# USB_TypeC_DRP.net
KiCad netlist of a schematic drawn in Altium Designer
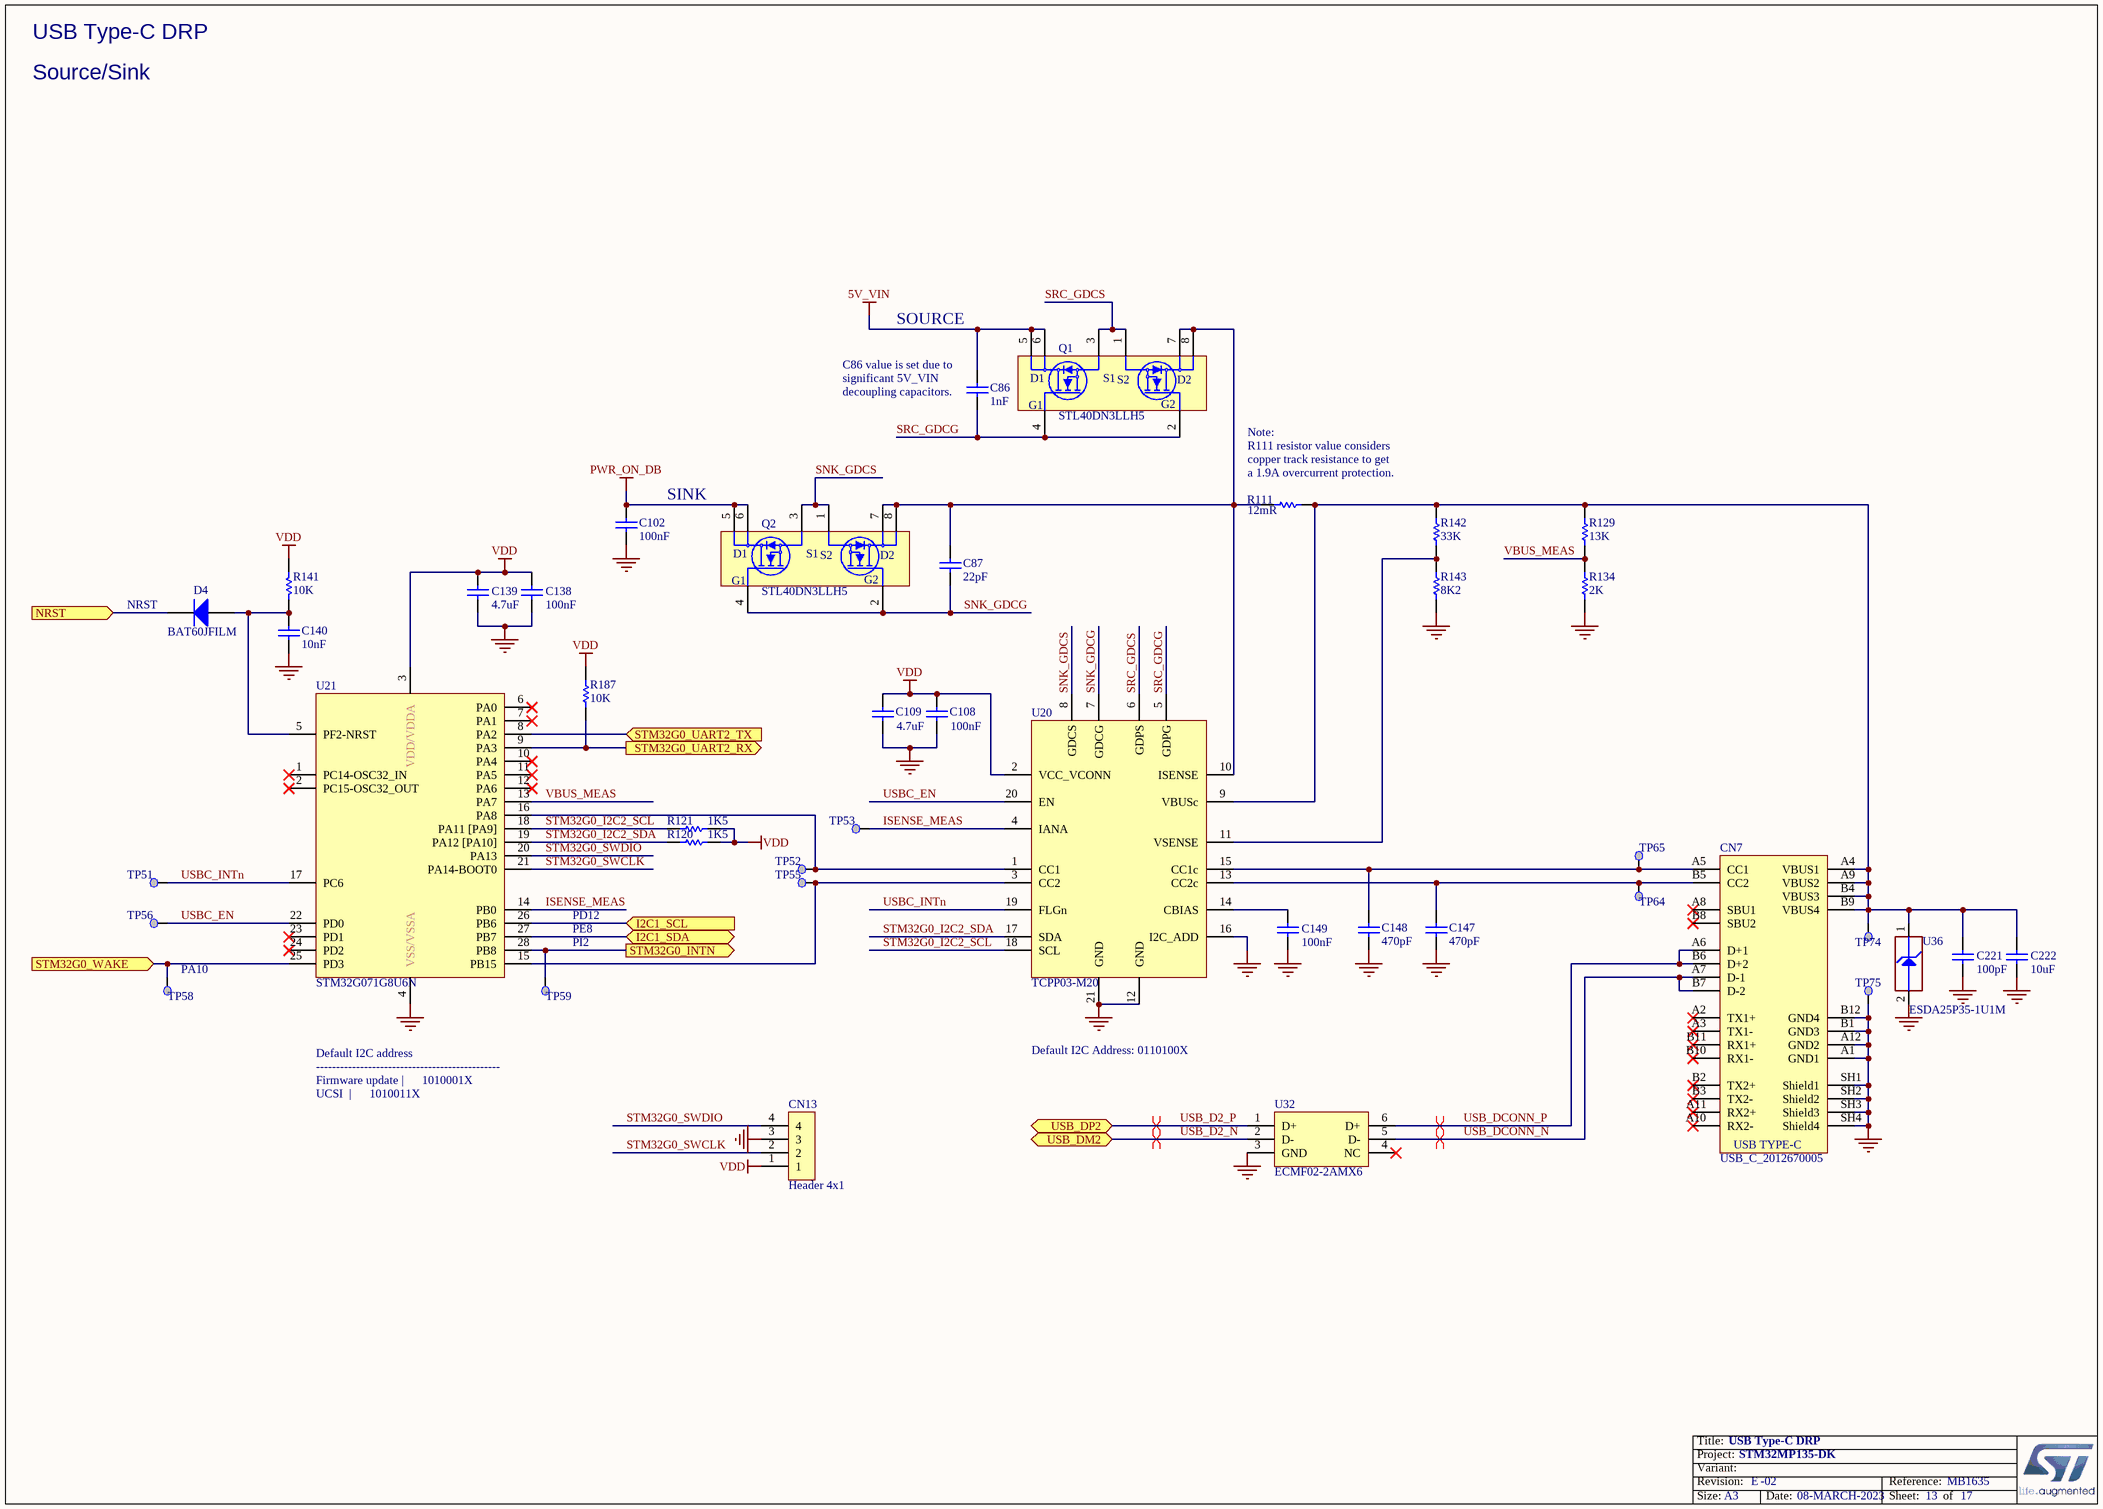
[diagram p0: USB_TypeC_DRP.SchDoc]

(export (version "E")
  (design (tool "Eeschema 10.0.6"))
  (components
    (comp (ref "C86")
      (value "1nF")
      (footprint "C0402")
      (description "Capacitor, MLCC, 1nF, 16V, X7R, +/-10%, 0402, T=0.5mm")
      (fields (field (name "INTERNAL_PART_NUMBER") "MCD-00198") (field (name "MANUFACTURER") "YAGEO"))
      (libsource (lib "MCD_PARTS_database") (part "Capacitor"))
    )
    (comp (ref "C87")
      (value "22pF")
      (footprint "C0402")
      (description "Capacitor, MLCC, 22pF, 50V, C0G, +/-5%, 0402, T=0.5mm")
      (fields (field (name "INTERNAL_PART_NUMBER") "MCD-01995") (field (name "MANUFACTURER") "TDK"))
      (libsource (lib "MCD_PARTS_database") (part "Capacitor"))
    )
    (comp (ref "C102")
      (value "100nF")
      (footprint "C0402")
      (description "Capacitor, MLCC, 100nF, 16V, X7R, +/-10%, 0402, T=0.5mm")
      (fields (field (name "INTERNAL_PART_NUMBER") "MCD-00006") (field (name "MANUFACTURER") "YAGEO"))
      (libsource (lib "MCD_PARTS_database") (part "Capacitor"))
    )
    (comp (ref "C108")
      (value "100nF")
      (footprint "C0402")
      (description "Capacitor, MLCC, 100nF, 16V, X7R, +/-10%, 0402, T=0.5mm")
      (fields (field (name "INTERNAL_PART_NUMBER") "MCD-00006") (field (name "MANUFACTURER") "YAGEO"))
      (libsource (lib "MCD_PARTS_database") (part "Capacitor"))
    )
    (comp (ref "C109")
      (value "4.7uF")
      (footprint "C0402")
      (description "Capacitor, MLCC, 4.7uF, 6V3, X5R, +/-20%, 0402, T=0.5mm")
      (fields (field (name "INTERNAL_PART_NUMBER") "MCD-01356") (field (name "MANUFACTURER") "MURATA"))
      (libsource (lib "MCD_PARTS_database") (part "Capacitor"))
    )
    (comp (ref "C138")
      (value "100nF")
      (footprint "C0402")
      (description "Capacitor, MLCC, 100nF, 16V, X7R, +/-10%, 0402, T=0.5mm")
      (fields (field (name "INTERNAL_PART_NUMBER") "MCD-00006") (field (name "MANUFACTURER") "YAGEO"))
      (libsource (lib "MCD_PARTS_database") (part "Capacitor"))
    )
    (comp (ref "C139")
      (value "4.7uF")
      (footprint "C0402")
      (description "Capacitor, MLCC, 4.7uF, 6V3, X5R, +/-20%, 0402, T=0.5mm")
      (fields (field (name "INTERNAL_PART_NUMBER") "MCD-01356") (field (name "MANUFACTURER") "MURATA"))
      (libsource (lib "MCD_PARTS_database") (part "Capacitor"))
    )
    (comp (ref "C140")
      (value "10nF")
      (footprint "C0402")
      (description "Capacitor, MLCC, 10nF, 50V, X7R, +/-10%, 0402, T=0.5mm")
      (fields (field (name "INTERNAL_PART_NUMBER") "MCD-02198") (field (name "MANUFACTURER") "YAGEO"))
      (libsource (lib "MCD_PARTS_database") (part "Capacitor"))
    )
    (comp (ref "C147")
      (value "470pF")
      (footprint "C0402")
      (description "Capacitor, MLCC, 470pF, 50V, NPO, +/-5%, 0402, T=0.5mm")
      (fields
        (field (name "INTERNAL_PART_NUMBER") "MCD-00724")
        (field (name "MANUFACTURER_PART_NUMBER") "CC0402JRNPO9BN471")
      )
      (libsource (lib "MCD_PARTS_database") (part "Capacitor"))
    )
    (comp (ref "C148")
      (value "470pF")
      (footprint "C0402")
      (description "Capacitor, MLCC, 470pF, 50V, NPO, +/-5%, 0402, T=0.5mm")
      (fields
        (field (name "INTERNAL_PART_NUMBER") "MCD-00724")
        (field (name "MANUFACTURER_PART_NUMBER") "CC0402JRNPO9BN471")
      )
      (libsource (lib "MCD_PARTS_database") (part "Capacitor"))
    )
    (comp (ref "C149")
      (value "100nF")
      (footprint "C0603")
      (description "Capacitor, MLCC, 100nF, 50V, X7R, +/-10%, 0603, T=0.8mm")
      (fields (field (name "INTERNAL_PART_NUMBER") "MCD-01099") (field (name "BMS_PART_NUMBER") "9142278"))
      (libsource (lib "MCD_PARTS_database") (part "Capacitor"))
    )
    (comp (ref "C221")
      (value "100pF")
      (footprint "C0402")
      (description "Capacitor, MLCC, 100pF, 50V, NPO, +/-5%, 0402, T=0.5mm")
      (fields
        (field (name "INTERNAL_PART_NUMBER") "MCD-00205")
        (field (name "MANUFACTURER_PART_NUMBER") "CC0402JRNPO9BN101")
      )
      (libsource (lib "MCD_PARTS_database") (part "Capacitor"))
    )
    (comp (ref "C222")
      (value "10uF")
      (footprint "C1210")
      (description "Capacitor, MLCC, 10uF, 50V, X7R, +/-10%, 1210, T=2.5mm")
      (fields
        (field (name "INTERNAL_PART_NUMBER") "MCD-02378")
        (field (name "MANUFACTURER_PART_NUMBER") "C3225X7R1H106K250AC")
      )
      (libsource (lib "MCD_PARTS_database") (part "Capacitor"))
    )
    (comp (ref "CN7")
      (value "USB_C_2012670005")
      (footprint "CON_USB-TYPEC_MOLEX_2012670005")
      (description "USB_TypeC, 24 pins, RA, SMD, T=3.71mm (USB Certified 3.1)")
      (fields
        (field (name "INTERNAL_PART_NUMBER") "MCD-02421")
        (field (name "MANUFACTURER_PART_NUMBER") "2012670005")
      )
      (libsource (lib "MCD_PARTS_database") (part "USB_TYPE_C_Receptacle"))
    )
    (comp (ref "CN13")
      (value "Header 4x1")
      (footprint "CON_SAMTEC_TSW-104-07-G-S")
      (description "Header, 4x1, 2.54mm, VR, TH, T=5.84mm/2.54mm")
      (fields
        (field (name "INTERNAL_PART_NUMBER") "MCD-00029")
        (field (name "MANUFACTURER_PART_NUMBER") "TSW-104-07-G-S")
      )
      (libsource (lib "MCD_PARTS_database") (part "Header 4x1"))
    )
    (comp (ref "D4")
      (value "BAT60JFILM")
      (footprint "DIO_SOD323")
      (fields
        (field (name "INTERNAL_PART_NUMBER") "MCD-00034")
        (field (name "BMS_PART_NUMBER") "9151097")
        (field (name "MANUFACTURER") "STMICROELECTRONICS")
      )
      (libsource (lib "MCD_PARTS_database") (part "BAT60JFILM"))
    )
    (comp (ref "Q1")
      (value "STL40DN3LLH5")
      (footprint "PowerFLAT_5x6")
      (description "MOSFET, Dual N-channel 30 V, 0.016 Ω typ., 40 A, STripFET™ H5 Power MOSFET")
      (fields
        (field (name "INTERNAL_PART_NUMBER") "MCD-02152")
        (field (name "MANUFACTURER") "STMICROELECTRONICS")
      )
      (libsource (lib "MCD_PARTS_database") (part "STL40DN3LLH5"))
    )
    (comp (ref "Q2")
      (value "STL40DN3LLH5")
      (footprint "PowerFLAT_5x6")
      (description "MOSFET, Dual N-channel 30 V, 0.016 Ω typ., 40 A, STripFET™ H5 Power MOSFET")
      (fields
        (field (name "INTERNAL_PART_NUMBER") "MCD-02152")
        (field (name "MANUFACTURER") "STMICROELECTRONICS")
      )
      (libsource (lib "MCD_PARTS_database") (part "STL40DN3LLH5"))
    )
    (comp (ref "R111")
      (value "12mR")
      (footprint "R0603_H070")
      (description "Resistor, 12mR, 0603, +/-1%, 1/2W")
      (fields (field (name "INTERNAL_PART_NUMBER") "MCD-03129") (field (name "MANUFACTURER") "VISHAY"))
      (libsource (lib "MCD_PARTS_database") (part "Resistor"))
    )
    (comp (ref "R120")
      (value "1K5")
      (footprint "R0402")
      (description "Resistor, 1K5, 0402, +/-1%, 1/16W")
      (fields (field (name "INTERNAL_PART_NUMBER") "MCD-00068") (field (name "MANUFACTURER") "YAGEO"))
      (libsource (lib "MCD_PARTS_database") (part "Resistor"))
    )
    (comp (ref "R121")
      (value "1K5")
      (footprint "R0402")
      (description "Resistor, 1K5, 0402, +/-1%, 1/16W")
      (fields (field (name "INTERNAL_PART_NUMBER") "MCD-00068") (field (name "MANUFACTURER") "YAGEO"))
      (libsource (lib "MCD_PARTS_database") (part "Resistor"))
    )
    (comp (ref "R129")
      (value "13K")
      (footprint "R0603")
      (description "Resistor, 13K, 0603,+/-1%, 1/10W")
      (fields (field (name "INTERNAL_PART_NUMBER") "MCD-00384") (field (name "MANUFACTURER") "YAGEO"))
      (libsource (lib "MCD_PARTS_database") (part "Resistor"))
    )
    (comp (ref "R134")
      (value "2K")
      (footprint "R0603")
      (description "Resistor, 2K ,0603, +/-1%, 1/10W")
      (fields (field (name "INTERNAL_PART_NUMBER") "MCD-00420") (field (name "MANUFACTURER") "YAGEO"))
      (libsource (lib "MCD_PARTS_database") (part "Resistor"))
    )
    (comp (ref "R141")
      (value "10K")
      (footprint "R0402")
      (description "Resistor, 10K, 0402, +/-1%, 1/16W")
      (fields (field (name "INTERNAL_PART_NUMBER") "MCD-00053") (field (name "BMS_PART_NUMBER") "9131590"))
      (libsource (lib "MCD_PARTS_database") (part "Resistor"))
    )
    (comp (ref "R142")
      (value "33K")
      (footprint "R0603")
      (description "Resistor, 33K, 0603, +/-1%, 1/10W")
      (fields (field (name "INTERNAL_PART_NUMBER") "MCD-00259") (field (name "BMS_PART_NUMBER") "9129771"))
      (libsource (lib "MCD_PARTS_database") (part "Resistor"))
    )
    (comp (ref "R143")
      (value "8K2")
      (footprint "R0603")
      (description "Resistor, 8K2, 0603, +/-1%, 1/10W")
      (fields (field (name "INTERNAL_PART_NUMBER") "MCD-00530") (field (name "MANUFACTURER") "YAGEO"))
      (libsource (lib "MCD_PARTS_database") (part "Resistor"))
    )
    (comp (ref "R187")
      (value "10K")
      (footprint "R0402")
      (description "Resistor, 10K, 0402, +/-1%, 1/16W")
      (fields
        (field (name "INTERNAL_PART_NUMBER") "MCD-00053")
        (field (name "MANUFACTURER_PART_NUMBER") "RC0402FR-0710KL")
      )
      (libsource (lib "MCD_PARTS_database") (part "Resistor"))
    )
    (comp (ref "TP51")
      (value "Test Point")
      (footprint "TP_SMD_1MM")
      (description "Test Point 1mm")
      (fields (field (name "INTERNAL_PART_NUMBER") "MCD-00074"))
      (libsource (lib "") (part "Test Point_2"))
    )
    (comp (ref "TP52")
      (value "Test Point")
      (footprint "TP_SMD_1MM")
      (description "Test Point 1mm")
      (fields (field (name "INTERNAL_PART_NUMBER") "MCD-00074"))
      (libsource (lib "") (part "Test Point_2"))
    )
    (comp (ref "TP53")
      (value "Test Point")
      (footprint "TP_SMD_1MM")
      (description "Test Point 1mm")
      (fields (field (name "INTERNAL_PART_NUMBER") "MCD-00074"))
      (libsource (lib "") (part "Test Point_2"))
    )
    (comp (ref "TP55")
      (value "Test Point")
      (footprint "TP_SMD_1MM")
      (description "Test Point 1mm")
      (fields (field (name "INTERNAL_PART_NUMBER") "MCD-00074"))
      (libsource (lib "") (part "Test Point_2"))
    )
    (comp (ref "TP56")
      (value "Test Point")
      (footprint "TP_SMD_1MM")
      (description "Test Point 1mm")
      (fields (field (name "INTERNAL_PART_NUMBER") "MCD-00074"))
      (libsource (lib "") (part "Test Point_2"))
    )
    (comp (ref "TP58")
      (value "Test Point")
      (footprint "TP_SMD_1MM")
      (description "Test Point 1mm")
      (fields (field (name "INTERNAL_PART_NUMBER") "MCD-00074"))
      (libsource (lib "MCD_PARTS_database") (part "Test Point"))
    )
    (comp (ref "TP59")
      (value "Test Point")
      (footprint "TP_SMD_1MM")
      (description "Test Point 1mm")
      (fields (field (name "INTERNAL_PART_NUMBER") "MCD-00074"))
      (libsource (lib "MCD_PARTS_database") (part "Test Point"))
    )
    (comp (ref "TP64")
      (value "Test Point")
      (footprint "TP_SMD_1MM")
      (description "Test Point 1mm")
      (fields (field (name "INTERNAL_PART_NUMBER") "MCD-00074"))
      (libsource (lib "MCD_PARTS_database") (part "Test Point"))
    )
    (comp (ref "TP65")
      (value "Test Point")
      (footprint "TP_SMD_1MM")
      (description "Test Point 1mm")
      (fields (field (name "INTERNAL_PART_NUMBER") "MCD-00074"))
      (libsource (lib "") (part "Test Point_1"))
    )
    (comp (ref "TP74")
      (value "Test Point")
      (footprint "TP_SMD_1MM")
      (description "Test Point 1mm")
      (fields (field (name "INTERNAL_PART_NUMBER") "MCD-00074"))
      (libsource (lib "MCD_PARTS_database") (part "Test Point"))
    )
    (comp (ref "TP75")
      (value "Test Point")
      (footprint "TP_SMD_1MM")
      (description "Test Point 1mm")
      (fields (field (name "INTERNAL_PART_NUMBER") "MCD-00074"))
      (libsource (lib "") (part "Test Point_1"))
    )
    (comp (ref "U20")
      (value "TCPP03-M20")
      (footprint "ICC_QFN20-EPAD_4X4_P050")
      (description "USB Type-C Port Protection for USB DRP Power Delivery, PPS compliant")
      (fields
        (field (name "INTERNAL_PART_NUMBER") "MCD-02130")
        (field (name "MANUFACTURER") "STMICROELECTRONICS")
      )
      (libsource (lib "MCD_PARTS_database") (part "TCPP03-M20"))
    )
    (comp (ref "U21")
      (value "STM32G071G8U6N")
      (footprint "ICC_UFQFPN28_4X4_P050")
      (fields
        (field (name "INTERNAL_PART_NUMBER") "MCD-02218")
        (field (name "MANUFACTURER") "STMICROELECTRONICS")
      )
      (libsource (lib "MCD_PARTS_database") (part "STM32G071G8U6N"))
    )
    (comp (ref "U32")
      (value "ECMF02-2AMX6")
      (footprint "ESD_QFN-6L_1P7X1P5_P050")
      (description "Common mode filter with ESD protection for USB 2.0 interface")
      (fields
        (field (name "INTERNAL_PART_NUMBER") "MCD-00649")
        (field (name "MANUFACTURER") "STMICROELECTRONICS")
      )
      (libsource (lib "MCD_PARTS_database") (part "ECMF02-2AMX6"))
    )
    (comp (ref "U36")
      (value "ESDA25P35-1U1M")
      (footprint "ESD_QFN1610_2N_1K_2A")
      (description "High power Transient voltage suppressor:25V/35A EOS and ESD transients protection.")
      (fields
        (field (name "INTERNAL_PART_NUMBER") "MCD-01207")
        (field (name "MANUFACTURER") "STMICROELECTRONICS")
      )
      (libsource (lib "MCD_PARTS_database") (part "ESD-TRANSIL"))
    )
  )
  (nets
    (net (code "1") (name "/I2C1_SCL") (class "Default")
      (node (ref "U21") (pin "26") (pinfunction "PB6_26") (pintype "passive"))
    )
    (net (code "2") (name "/I2C1_SDA") (class "Default")
      (node (ref "U21") (pin "27") (pinfunction "PB7_27") (pintype "passive"))
    )
    (net (code "3") (name "/ISENSE_MEAS") (class "Default")
      (node (ref "TP53") (pin "1") (pinfunction "1_1") (pintype "passive"))
      (node (ref "U20") (pin "4") (pinfunction "IANA_4") (pintype "passive"))
      (node (ref "U21") (pin "14") (pinfunction "PB0_14") (pintype "passive"))
    )
    (net (code "4") (name "/NRST") (class "Default")
      (node (ref "D4") (pin "2") (pinfunction "K_2") (pintype "passive"))
    )
    (net (code "5") (name "/SNK_GDCG") (class "Default")
      (node (ref "C87") (pin "1") (pinfunction "1_1") (pintype "passive"))
      (node (ref "Q2") (pin "2") (pinfunction "G2_2") (pintype "passive"))
      (node (ref "Q2") (pin "4") (pinfunction "G1_4") (pintype "passive"))
      (node (ref "U20") (pin "7") (pinfunction "GDCG_7") (pintype "passive"))
    )
    (net (code "6") (name "/SNK_GDCS") (class "Default")
      (node (ref "Q2") (pin "1") (pinfunction "S2_1") (pintype "passive"))
      (node (ref "Q2") (pin "3") (pinfunction "S1_3") (pintype "passive"))
      (node (ref "U20") (pin "8") (pinfunction "GDCS_8") (pintype "passive"))
    )
    (net (code "7") (name "/SRC_GDCG") (class "Default")
      (node (ref "C86") (pin "1") (pinfunction "1_1") (pintype "passive"))
      (node (ref "Q1") (pin "2") (pinfunction "G2_2") (pintype "passive"))
      (node (ref "Q1") (pin "4") (pinfunction "G1_4") (pintype "passive"))
      (node (ref "U20") (pin "5") (pinfunction "GDPG_5") (pintype "passive"))
    )
    (net (code "8") (name "/SRC_GDCS") (class "Default")
      (node (ref "Q1") (pin "1") (pinfunction "S2_1") (pintype "passive"))
      (node (ref "Q1") (pin "3") (pinfunction "S1_3") (pintype "passive"))
      (node (ref "U20") (pin "6") (pinfunction "GDPS_6") (pintype "passive"))
    )
    (net (code "9") (name "/STM32G0_I2C2_SCL") (class "Default")
      (node (ref "R121") (pin "2") (pinfunction "2_2") (pintype "passive"))
      (node (ref "U20") (pin "18") (pinfunction "SCL_18") (pintype "passive"))
      (node (ref "U21") (pin "18") (pinfunction "PA11_[PA9]_18") (pintype "passive"))
    )
    (net (code "10") (name "/STM32G0_I2C2_SDA") (class "Default")
      (node (ref "R120") (pin "1") (pinfunction "1_1") (pintype "passive"))
      (node (ref "U20") (pin "17") (pinfunction "SDA_17") (pintype "passive"))
      (node (ref "U21") (pin "19") (pinfunction "PA12_[PA10]_19") (pintype "passive"))
    )
    (net (code "11") (name "/STM32G0_INTN") (class "Default")
      (node (ref "TP59") (pin "1") (pinfunction "1_1") (pintype "passive"))
      (node (ref "U21") (pin "28") (pinfunction "PB8_28") (pintype "passive"))
    )
    (net (code "12") (name "/STM32G0_SWCLK") (class "Default")
      (node (ref "CN13") (pin "2") (pinfunction "2_2") (pintype "passive"))
      (node (ref "U21") (pin "21") (pinfunction "PA14-BOOT0_21") (pintype "passive"))
    )
    (net (code "13") (name "/STM32G0_SWDIO") (class "Default")
      (node (ref "CN13") (pin "4") (pinfunction "4_4") (pintype "passive"))
      (node (ref "U21") (pin "20") (pinfunction "PA13_20") (pintype "passive"))
    )
    (net (code "14") (name "/STM32G0_UART2_RX") (class "Default")
      (node (ref "R187") (pin "1") (pinfunction "1_1") (pintype "passive"))
      (node (ref "U21") (pin "9") (pinfunction "PA3_9") (pintype "passive"))
    )
    (net (code "15") (name "/STM32G0_UART2_TX") (class "Default")
      (node (ref "U21") (pin "8") (pinfunction "PA2_8") (pintype "passive"))
    )
    (net (code "16") (name "/STM32G0_WAKE") (class "Default")
      (node (ref "TP58") (pin "1") (pinfunction "1_1") (pintype "passive"))
      (node (ref "U21") (pin "25") (pinfunction "PD3_25") (pintype "passive"))
    )
    (net (code "17") (name "/USBC_EN") (class "Default")
      (node (ref "TP56") (pin "1") (pinfunction "1_1") (pintype "passive"))
      (node (ref "U20") (pin "20") (pinfunction "EN_20") (pintype "passive"))
      (node (ref "U21") (pin "22") (pinfunction "PD0_22") (pintype "passive"))
    )
    (net (code "18") (name "/USBC_INTn") (class "Default")
      (node (ref "TP51") (pin "1") (pinfunction "1_1") (pintype "passive"))
      (node (ref "U20") (pin "19") (pinfunction "FLGn_19") (pintype "passive"))
      (node (ref "U21") (pin "17") (pinfunction "PC6_17") (pintype "passive"))
    )
    (net (code "19") (name "/USB_D2_N") (class "Default")
      (node (ref "U32") (pin "2") (pinfunction "D-_2") (pintype "passive"))
    )
    (net (code "20") (name "/USB_D2_P") (class "Default")
      (node (ref "U32") (pin "1") (pinfunction "D+_1") (pintype "passive"))
    )
    (net (code "21") (name "/USB_DCONN_N") (class "Default")
      (node (ref "CN7") (pin "A7") (pinfunction "D-1_A7") (pintype "passive"))
      (node (ref "CN7") (pin "B7") (pinfunction "D-2_B7") (pintype "passive"))
      (node (ref "U32") (pin "5") (pinfunction "D-_5") (pintype "passive"))
    )
    (net (code "22") (name "/USB_DCONN_P") (class "Default")
      (node (ref "CN7") (pin "A6") (pinfunction "D+1_A6") (pintype "passive"))
      (node (ref "CN7") (pin "B6") (pinfunction "D+2_B6") (pintype "passive"))
      (node (ref "U32") (pin "6") (pinfunction "D+_6") (pintype "passive"))
    )
    (net (code "23") (name "/VBUS_MEAS") (class "Default")
      (node (ref "R129") (pin "1") (pinfunction "1_1") (pintype "passive"))
      (node (ref "R134") (pin "2") (pinfunction "2_2") (pintype "passive"))
      (node (ref "U21") (pin "13") (pinfunction "PA7_13") (pintype "passive"))
    )
    (net (code "24") (name "5V_VIN") (class "Default")
      (node (ref "C86") (pin "2") (pinfunction "2_2") (pintype "passive"))
      (node (ref "Q1") (pin "5") (pinfunction "D1_5") (pintype "passive"))
      (node (ref "Q1") (pin "6") (pinfunction "D1_6") (pintype "passive"))
    )
    (net (code "25") (name "GND") (class "Default")
      (node (ref "C102") (pin "1") (pinfunction "1_1") (pintype "passive"))
      (node (ref "C108") (pin "1") (pinfunction "1_1") (pintype "passive"))
      (node (ref "C109") (pin "1") (pinfunction "1_1") (pintype "passive"))
      (node (ref "C138") (pin "1") (pinfunction "1_1") (pintype "passive"))
      (node (ref "C139") (pin "1") (pinfunction "1_1") (pintype "passive"))
      (node (ref "C140") (pin "1") (pinfunction "1_1") (pintype "passive"))
      (node (ref "C147") (pin "1") (pinfunction "1_1") (pintype "passive"))
      (node (ref "C148") (pin "1") (pinfunction "1_1") (pintype "passive"))
      (node (ref "C149") (pin "1") (pinfunction "1_1") (pintype "passive"))
      (node (ref "C221") (pin "1") (pinfunction "1_1") (pintype "passive"))
      (node (ref "C222") (pin "1") (pinfunction "1_1") (pintype "passive"))
      (node (ref "CN13") (pin "3") (pinfunction "3_3") (pintype "passive"))
      (node (ref "CN7") (pin "A1") (pinfunction "GND1_A1") (pintype "passive"))
      (node (ref "CN7") (pin "A12") (pinfunction "GND2_A12") (pintype "passive"))
      (node (ref "CN7") (pin "B1") (pinfunction "GND3_B1") (pintype "passive"))
      (node (ref "CN7") (pin "B12") (pinfunction "GND4_B12") (pintype "passive"))
      (node (ref "CN7") (pin "SH1") (pinfunction "Shield1_SH1") (pintype "passive"))
      (node (ref "CN7") (pin "SH2") (pinfunction "Shield2_SH2") (pintype "passive"))
      (node (ref "CN7") (pin "SH3") (pinfunction "Shield3_SH3") (pintype "passive"))
      (node (ref "CN7") (pin "SH4") (pinfunction "Shield4_SH4") (pintype "passive"))
      (node (ref "R134") (pin "1") (pinfunction "1_1") (pintype "passive"))
      (node (ref "R143") (pin "1") (pinfunction "1_1") (pintype "passive"))
      (node (ref "TP75") (pin "1") (pinfunction "1_1") (pintype "passive"))
      (node (ref "U20") (pin "12") (pinfunction "GND_12") (pintype "passive"))
      (node (ref "U20") (pin "16") (pinfunction "I2C_ADD_16") (pintype "passive"))
      (node (ref "U20") (pin "21") (pinfunction "GND_21") (pintype "passive"))
      (node (ref "U21") (pin "4") (pinfunction "VSS/VSSA_4") (pintype "passive"))
      (node (ref "U32") (pin "3") (pinfunction "GND_3") (pintype "passive"))
      (node (ref "U36") (pin "2") (pinfunction "GND_2") (pintype "passive"))
    )
    (net (code "26") (name "Net-(CN7-CC1)") (class "Default")
      (node (ref "C148") (pin "2") (pinfunction "2_2") (pintype "passive"))
      (node (ref "CN7") (pin "A5") (pinfunction "CC1_A5") (pintype "passive"))
      (node (ref "TP65") (pin "1") (pinfunction "1_1") (pintype "passive"))
      (node (ref "U20") (pin "15") (pinfunction "CC1c_15") (pintype "passive"))
    )
    (net (code "27") (name "Net-(CN7-CC2)") (class "Default")
      (node (ref "C147") (pin "2") (pinfunction "2_2") (pintype "passive"))
      (node (ref "CN7") (pin "B5") (pinfunction "CC2_B5") (pintype "passive"))
      (node (ref "TP64") (pin "1") (pinfunction "1_1") (pintype "passive"))
      (node (ref "U20") (pin "13") (pinfunction "CC2c_13") (pintype "passive"))
    )
    (net (code "28") (name "Net-(CN7-VBUS1)") (class "Default")
      (node (ref "C221") (pin "2") (pinfunction "2_2") (pintype "passive"))
      (node (ref "C222") (pin "2") (pinfunction "2_2") (pintype "passive"))
      (node (ref "CN7") (pin "A4") (pinfunction "VBUS1_A4") (pintype "passive"))
      (node (ref "CN7") (pin "A9") (pinfunction "VBUS2_A9") (pintype "passive"))
      (node (ref "CN7") (pin "B4") (pinfunction "VBUS3_B4") (pintype "passive"))
      (node (ref "CN7") (pin "B9") (pinfunction "VBUS4_B9") (pintype "passive"))
      (node (ref "R111") (pin "1") (pinfunction "1_1") (pintype "passive"))
      (node (ref "R129") (pin "2") (pinfunction "2_2") (pintype "passive"))
      (node (ref "R142") (pin "2") (pinfunction "2_2") (pintype "passive"))
      (node (ref "TP74") (pin "1") (pinfunction "1_1") (pintype "passive"))
      (node (ref "U20") (pin "9") (pinfunction "VBUSc_9") (pintype "passive"))
      (node (ref "U36") (pin "1") (pinfunction "IO1_1") (pintype "passive"))
    )
    (net (code "29") (name "Net-(D4-A)") (class "Default")
      (node (ref "C140") (pin "2") (pinfunction "2_2") (pintype "passive"))
      (node (ref "D4") (pin "1") (pinfunction "A_1") (pintype "passive"))
      (node (ref "R141") (pin "1") (pinfunction "1_1") (pintype "passive"))
      (node (ref "U21") (pin "5") (pinfunction "PF2-NRST_5") (pintype "passive"))
    )
    (net (code "30") (name "Net-(U20-CBIAS)") (class "Default")
      (node (ref "C149") (pin "2") (pinfunction "2_2") (pintype "passive"))
      (node (ref "U20") (pin "14") (pinfunction "CBIAS_14") (pintype "passive"))
    )
    (net (code "31") (name "Net-(U20-CC1)") (class "Default")
      (node (ref "TP52") (pin "1") (pinfunction "1_1") (pintype "passive"))
      (node (ref "U20") (pin "1") (pinfunction "CC1_1") (pintype "passive"))
      (node (ref "U21") (pin "16") (pinfunction "PA8_16") (pintype "passive"))
    )
    (net (code "32") (name "Net-(U20-CC2)") (class "Default")
      (node (ref "TP55") (pin "1") (pinfunction "1_1") (pintype "passive"))
      (node (ref "U20") (pin "3") (pinfunction "CC2_3") (pintype "passive"))
      (node (ref "U21") (pin "15") (pinfunction "PB15_15") (pintype "passive"))
    )
    (net (code "33") (name "Net-(U20-ISENSE)") (class "Default")
      (node (ref "C87") (pin "2") (pinfunction "2_2") (pintype "passive"))
      (node (ref "Q1") (pin "7") (pinfunction "D2_7") (pintype "passive"))
      (node (ref "Q1") (pin "8") (pinfunction "D2_8") (pintype "passive"))
      (node (ref "Q2") (pin "7") (pinfunction "D2_7") (pintype "passive"))
      (node (ref "Q2") (pin "8") (pinfunction "D2_8") (pintype "passive"))
      (node (ref "R111") (pin "2") (pinfunction "2_2") (pintype "passive"))
      (node (ref "U20") (pin "10") (pinfunction "ISENSE_10") (pintype "passive"))
    )
    (net (code "34") (name "Net-(U20-VSENSE)") (class "Default")
      (node (ref "R142") (pin "1") (pinfunction "1_1") (pintype "passive"))
      (node (ref "R143") (pin "2") (pinfunction "2_2") (pintype "passive"))
      (node (ref "U20") (pin "11") (pinfunction "VSENSE_11") (pintype "passive"))
    )
    (net (code "35") (name "PWR_ON_DB") (class "Default")
      (node (ref "C102") (pin "2") (pinfunction "2_2") (pintype "passive"))
      (node (ref "Q2") (pin "5") (pinfunction "D1_5") (pintype "passive"))
      (node (ref "Q2") (pin "6") (pinfunction "D1_6") (pintype "passive"))
    )
    (net (code "36") (name "VDD") (class "Default")
      (node (ref "C108") (pin "2") (pinfunction "2_2") (pintype "passive"))
      (node (ref "C109") (pin "2") (pinfunction "2_2") (pintype "passive"))
      (node (ref "C138") (pin "2") (pinfunction "2_2") (pintype "passive"))
      (node (ref "C139") (pin "2") (pinfunction "2_2") (pintype "passive"))
      (node (ref "CN13") (pin "1") (pinfunction "1_1") (pintype "passive"))
      (node (ref "R120") (pin "2") (pinfunction "2_2") (pintype "passive"))
      (node (ref "R121") (pin "1") (pinfunction "1_1") (pintype "passive"))
      (node (ref "R141") (pin "2") (pinfunction "2_2") (pintype "passive"))
      (node (ref "R187") (pin "2") (pinfunction "2_2") (pintype "passive"))
      (node (ref "U20") (pin "2") (pinfunction "VCC_VCONN_2") (pintype "passive"))
      (node (ref "U21") (pin "3") (pinfunction "VDD/VDDA_3") (pintype "passive"))
    )
    (net (code "37") (name "unconnected-(CN7-RX1+-PadB11)") (class "Default")
      (node (ref "CN7") (pin "B11") (pinfunction "RX1+_B11") (pintype "passive+no_connect"))
    )
    (net (code "38") (name "unconnected-(CN7-RX1--PadB10)") (class "Default")
      (node (ref "CN7") (pin "B10") (pinfunction "RX1-_B10") (pintype "passive+no_connect"))
    )
    (net (code "39") (name "unconnected-(CN7-RX2+-PadA11)") (class "Default")
      (node (ref "CN7") (pin "A11") (pinfunction "RX2+_A11") (pintype "passive+no_connect"))
    )
    (net (code "40") (name "unconnected-(CN7-RX2--PadA10)") (class "Default")
      (node (ref "CN7") (pin "A10") (pinfunction "RX2-_A10") (pintype "passive+no_connect"))
    )
    (net (code "41") (name "unconnected-(CN7-SBU1-PadA8)") (class "Default")
      (node (ref "CN7") (pin "A8") (pinfunction "SBU1_A8") (pintype "passive+no_connect"))
    )
    (net (code "42") (name "unconnected-(CN7-SBU2-PadB8)") (class "Default")
      (node (ref "CN7") (pin "B8") (pinfunction "SBU2_B8") (pintype "passive+no_connect"))
    )
    (net (code "43") (name "unconnected-(CN7-TX1+-PadA2)") (class "Default")
      (node (ref "CN7") (pin "A2") (pinfunction "TX1+_A2") (pintype "passive+no_connect"))
    )
    (net (code "44") (name "unconnected-(CN7-TX1--PadA3)") (class "Default")
      (node (ref "CN7") (pin "A3") (pinfunction "TX1-_A3") (pintype "passive+no_connect"))
    )
    (net (code "45") (name "unconnected-(CN7-TX2+-PadB2)") (class "Default")
      (node (ref "CN7") (pin "B2") (pinfunction "TX2+_B2") (pintype "passive+no_connect"))
    )
    (net (code "46") (name "unconnected-(CN7-TX2--PadB3)") (class "Default")
      (node (ref "CN7") (pin "B3") (pinfunction "TX2-_B3") (pintype "passive+no_connect"))
    )
    (net (code "47") (name "unconnected-(U21-PA0-Pad6)") (class "Default")
      (node (ref "U21") (pin "6") (pinfunction "PA0_6") (pintype "passive+no_connect"))
    )
    (net (code "48") (name "unconnected-(U21-PA1-Pad7)") (class "Default")
      (node (ref "U21") (pin "7") (pinfunction "PA1_7") (pintype "passive+no_connect"))
    )
    (net (code "49") (name "unconnected-(U21-PA4-Pad10)") (class "Default")
      (node (ref "U21") (pin "10") (pinfunction "PA4_10") (pintype "passive+no_connect"))
    )
    (net (code "50") (name "unconnected-(U21-PA5-Pad11)") (class "Default")
      (node (ref "U21") (pin "11") (pinfunction "PA5_11") (pintype "passive+no_connect"))
    )
    (net (code "51") (name "unconnected-(U21-PA6-Pad12)") (class "Default")
      (node (ref "U21") (pin "12") (pinfunction "PA6_12") (pintype "passive+no_connect"))
    )
    (net (code "52") (name "unconnected-(U21-PC14-OSC32_IN-Pad1)") (class "Default")
      (node (ref "U21") (pin "1") (pinfunction "PC14-OSC32_IN_1") (pintype "passive+no_connect"))
    )
    (net (code "53") (name "unconnected-(U21-PC15-OSC32_OUT-Pad2)") (class "Default")
      (node (ref "U21") (pin "2") (pinfunction "PC15-OSC32_OUT_2") (pintype "passive+no_connect"))
    )
    (net (code "54") (name "unconnected-(U21-PD1-Pad23)") (class "Default")
      (node (ref "U21") (pin "23") (pinfunction "PD1_23") (pintype "passive+no_connect"))
    )
    (net (code "55") (name "unconnected-(U21-PD2-Pad24)") (class "Default")
      (node (ref "U21") (pin "24") (pinfunction "PD2_24") (pintype "passive+no_connect"))
    )
    (net (code "56") (name "unconnected-(U32-NC-Pad4)") (class "Default")
      (node (ref "U32") (pin "4") (pinfunction "NC_4") (pintype "passive+no_connect"))
    )
  )
)
